# Stepper_driver_lowcost.net
KiCad netlist of a schematic drawn in Altium Designer
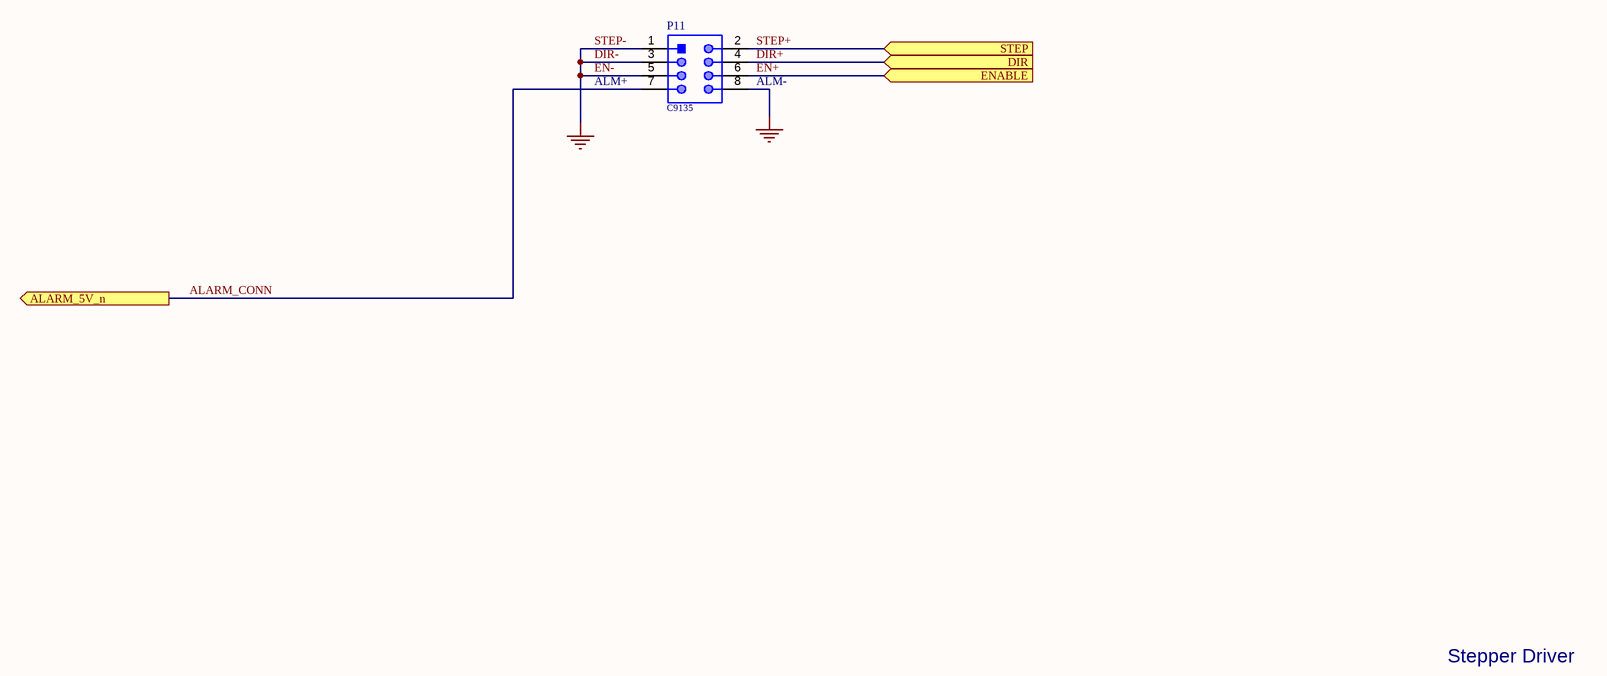
[diagram p0: Stepper_driver_lowcost.SchDoc]

(export (version "E")
  (design (tool "Eeschema 10.0.6"))
  (components
    (comp (ref "P11")
      (value "C9135")
      (footprint "61200821621")
      (description "Male Box Header WR-BHD, THT, Vertical, pitch 2.54 mm, 8 pins")
      (fields (field (name "MANUFACTURER") "Wurth Elektronik") (field (name "PUBLISHER") "WurthElektronik"))
      (libsource (lib "Altium Content Vault") (part "WE-CN-2P-M-R8"))
    )
  )
  (nets
    (net (code "1") (name "/ALARM_CONN") (class "Default")
      (node (ref "P11") (pin "7") (pinfunction "7_7") (pintype "passive"))
    )
    (net (code "2") (name "/DIR+") (class "Default")
      (node (ref "P11") (pin "4") (pinfunction "4_4") (pintype "passive"))
    )
    (net (code "3") (name "/EN+") (class "Default")
      (node (ref "P11") (pin "6") (pinfunction "6_6") (pintype "passive"))
    )
    (net (code "4") (name "/STEP+") (class "Default")
      (node (ref "P11") (pin "2") (pinfunction "2_2") (pintype "passive"))
    )
    (net (code "5") (name "GND") (class "Default")
      (node (ref "P11") (pin "1") (pinfunction "1_1") (pintype "passive"))
      (node (ref "P11") (pin "3") (pinfunction "3_3") (pintype "passive"))
      (node (ref "P11") (pin "5") (pinfunction "5_5") (pintype "passive"))
      (node (ref "P11") (pin "8") (pinfunction "8_8") (pintype "passive"))
    )
  )
)
